# WT108_Output.net
KiCad netlist of a schematic drawn in Altium Designer
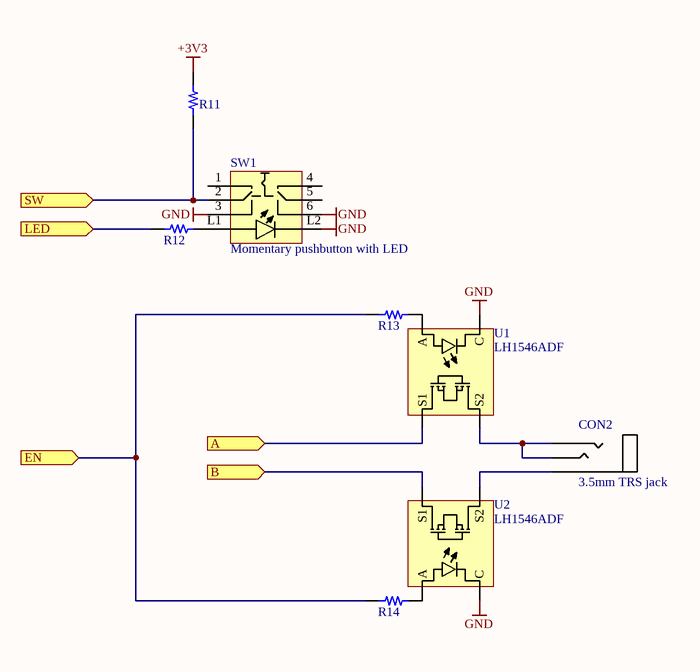
[diagram p0: WT108_Output.schdoc]

(export (version "E")
  (design (tool "Eeschema 10.0.6"))
  (components
    (comp (ref "CON2")
      (value "3.5mm TRS jack")
      (footprint "3.5mm socket, side mount")
      (libsource (lib "7c7_Connectors") (part "3.5mm TRS jack"))
    )
    (comp (ref "R11")
      (value "10 kOhms")
      (footprint "RES 0603_1608")
      (description "RES SMD 10K OHM 0.5% 1/10W 0603")
      (fields (field (name "MANUFACTURER") "Yageo") (field (name "PART NUMBER") "RT0603DRD0710KL"))
      (libsource (lib "Celestial Altium Library") (part "Resistor"))
    )
    (comp (ref "R12")
      (value "120 Ohms")
      (footprint "RES 0603_1608")
      (description "RES SMD 120 OHM 0.5% 1/10W 0603")
      (fields (field (name "MANUFACTURER") "Yageo") (field (name "PART NUMBER") "RT0603DRE07120RL"))
      (libsource (lib "Celestial Altium Library") (part "Resistor"))
    )
    (comp (ref "R13")
      (value "120 Ohms")
      (footprint "RES 0603_1608")
      (description "RES SMD 120 OHM 0.5% 1/10W 0603")
      (fields (field (name "MANUFACTURER") "Yageo") (field (name "PART NUMBER") "RT0603DRE07120RL"))
      (libsource (lib "Celestial Altium Library") (part "Resistor"))
    )
    (comp (ref "R14")
      (value "120 Ohms")
      (footprint "RES 0603_1608")
      (description "RES SMD 120 OHM 0.5% 1/10W 0603")
      (fields (field (name "MANUFACTURER") "Yageo") (field (name "PART NUMBER") "RT0603DRE07120RL"))
      (libsource (lib "Celestial Altium Library") (part "Resistor"))
    )
    (comp (ref "SW1")
      (value "Momentary pushbutton with LED")
      (footprint "Switch_with_LED")
      (libsource (lib "7c7_electromechanical") (part "MCPSD7x"))
    )
    (comp (ref "U1")
      (value "LH1546ADF")
      (footprint "LH1546")
      (description "1 Form A Solid-State Relay (Normally Open) 22Ohm 350V")
      (libsource (lib "") (part "LH1546ADF_1"))
    )
    (comp (ref "U2")
      (value "LH1546ADF")
      (footprint "LH1546")
      (description "1 Form A Solid-State Relay (Normally Open) 22Ohm 350V")
      (libsource (lib "7c7_IntegratedCircuits") (part "LH1546ADF"))
    )
  )
  (nets
    (net (code "1") (name "+3V3") (class "Default")
      (node (ref "R11") (pin "2") (pinfunction "2_2") (pintype "passive"))
    )
    (net (code "2") (name "/A") (class "Default")
      (node (ref "U1") (pin "4") (pinfunction "S1_4") (pintype "passive"))
    )
    (net (code "3") (name "/B") (class "Default")
      (node (ref "U2") (pin "4") (pinfunction "S1_4") (pintype "passive"))
    )
    (net (code "4") (name "/EN") (class "Default")
      (node (ref "R13") (pin "1") (pinfunction "1_1") (pintype "passive"))
      (node (ref "R14") (pin "1") (pinfunction "1_1") (pintype "passive"))
    )
    (net (code "5") (name "/LED") (class "Default")
      (node (ref "R12") (pin "1") (pinfunction "1_1") (pintype "passive"))
    )
    (net (code "6") (name "/SW") (class "Default")
      (node (ref "R11") (pin "1") (pinfunction "1_1") (pintype "passive"))
      (node (ref "SW1") (pin "2") (pinfunction "2_2") (pintype "passive"))
    )
    (net (code "7") (name "GND") (class "Default")
      (node (ref "SW1") (pin "3") (pinfunction "3_3") (pintype "passive"))
      (node (ref "SW1") (pin "6") (pinfunction "6_6") (pintype "passive"))
      (node (ref "SW1") (pin "L2") (pinfunction "C_L2") (pintype "passive"))
      (node (ref "U1") (pin "2") (pinfunction "C_2") (pintype "passive"))
      (node (ref "U2") (pin "2") (pinfunction "C_2") (pintype "passive"))
    )
    (net (code "8") (name "Net-(SW1-A)") (class "Default")
      (node (ref "R12") (pin "2") (pinfunction "2_2") (pintype "passive"))
      (node (ref "SW1") (pin "L1") (pinfunction "A_L1") (pintype "passive"))
    )
    (net (code "9") (name "Net-(U1-A)") (class "Default")
      (node (ref "R13") (pin "2") (pinfunction "2_2") (pintype "passive"))
      (node (ref "U1") (pin "1") (pinfunction "A_1") (pintype "passive"))
    )
    (net (code "10") (name "Net-(U1-S2)") (class "Default")
      (node (ref "CON2") (pin "R") (pinfunction "R_R") (pintype "passive"))
      (node (ref "CON2") (pin "T") (pinfunction "T_T") (pintype "passive"))
      (node (ref "U1") (pin "3") (pinfunction "S2_3") (pintype "passive"))
    )
    (net (code "11") (name "Net-(U2-A)") (class "Default")
      (node (ref "R14") (pin "2") (pinfunction "2_2") (pintype "passive"))
      (node (ref "U2") (pin "1") (pinfunction "A_1") (pintype "passive"))
    )
    (net (code "12") (name "Net-(U2-S2)") (class "Default")
      (node (ref "CON2") (pin "S") (pinfunction "S_S") (pintype "passive"))
      (node (ref "U2") (pin "3") (pinfunction "S2_3") (pintype "passive"))
    )
    (net (code "13") (name "unconnected-(SW1-7-Pad1)") (class "Default")
      (node (ref "SW1") (pin "1") (pinfunction "7_1") (pintype "passive"))
    )
    (net (code "14") (name "unconnected-(SW1-Pad4)") (class "Default")
      (node (ref "SW1") (pin "4") (pinfunction "4_4") (pintype "passive"))
    )
    (net (code "15") (name "unconnected-(SW1-Pad5)") (class "Default")
      (node (ref "SW1") (pin "5") (pinfunction "5_5") (pintype "passive"))
    )
  )
)
